# SH5_-_LOAD_MONITORING_1.net
KiCad netlist of a schematic drawn in Altium Designer
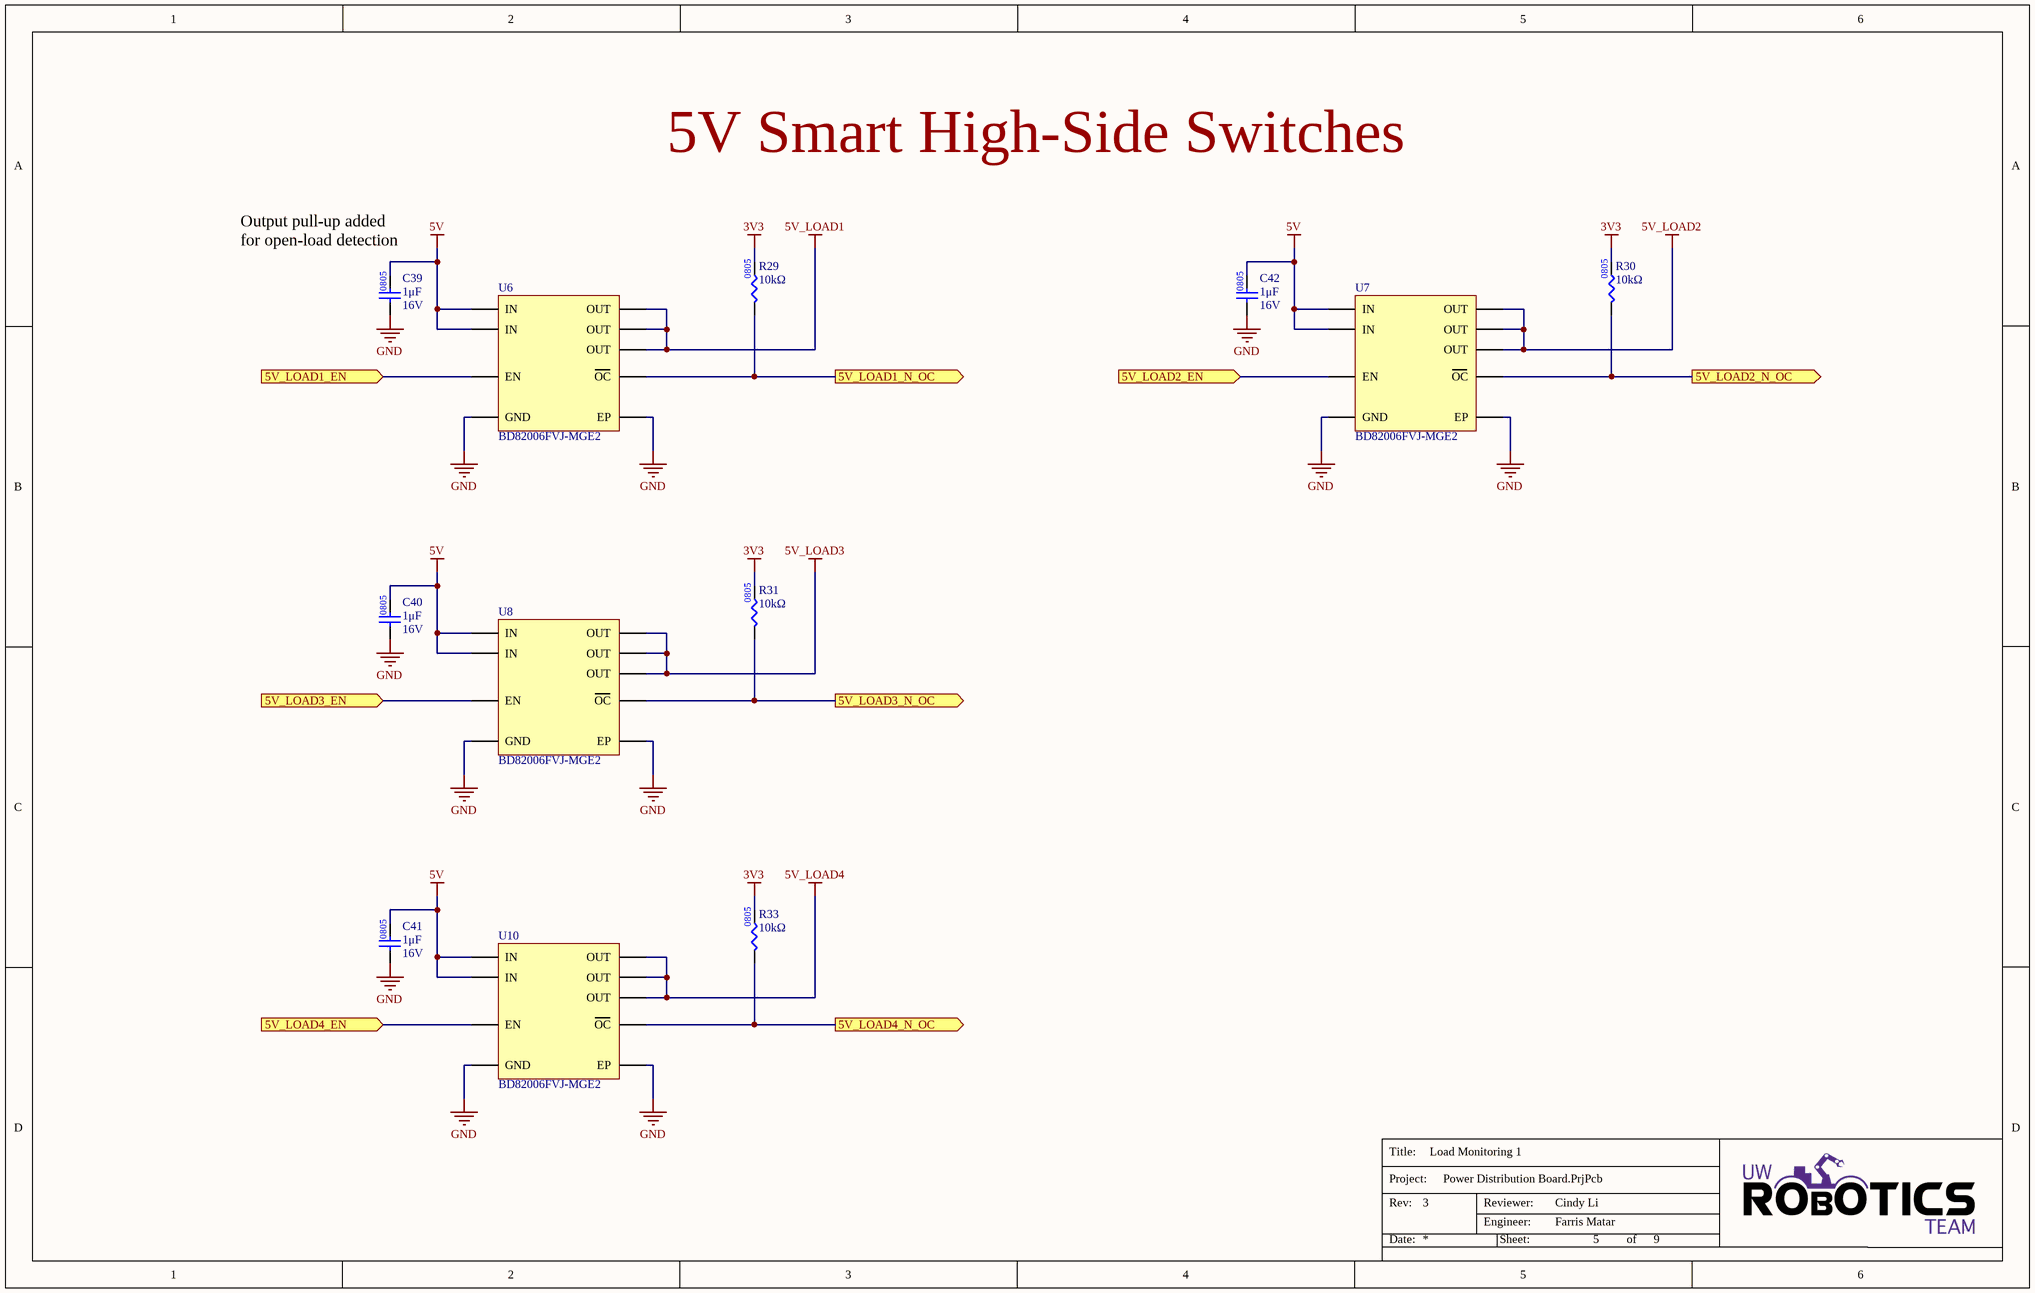
[diagram p0: SH5 - LOAD MONITORING 1.SchDoc]

(export (version "E")
  (design (tool "Eeschema 10.0.6"))
  (components
    (comp (ref "C39")
      (value "1μF")
      (footprint "CAP0805")
      (description "CAP CER 1UF 16V X7R 0805")
      (fields (field (name "VOLTAGE RATING") "16V") (field (name "Comment") "CAP_1uF_16V_0805"))
      (libsource (lib "UWRT_Schematic_Library_2020") (part "CAP_1uF_16V_0805"))
    )
    (comp (ref "C40")
      (value "1μF")
      (footprint "CAP0805")
      (description "CAP CER 1UF 16V X7R 0805")
      (fields (field (name "VOLTAGE RATING") "16V") (field (name "Comment") "CAP_1uF_16V_0805"))
      (libsource (lib "UWRT_Schematic_Library_2020") (part "CAP_1uF_16V_0805"))
    )
    (comp (ref "C41")
      (value "1μF")
      (footprint "CAP0805")
      (description "CAP CER 1UF 16V X7R 0805")
      (fields (field (name "VOLTAGE RATING") "16V") (field (name "Comment") "CAP_1uF_16V_0805"))
      (libsource (lib "UWRT_Schematic_Library_2020") (part "CAP_1uF_16V_0805"))
    )
    (comp (ref "C42")
      (value "1μF")
      (footprint "CAP0805")
      (description "CAP CER 1UF 16V X7R 0805")
      (fields (field (name "VOLTAGE RATING") "16V") (field (name "Comment") "CAP_1uF_16V_0805"))
      (libsource (lib "UWRT_Schematic_Library_2020") (part "CAP_1uF_16V_0805"))
    )
    (comp (ref "R29")
      (value "10kΩ")
      (footprint "RES0805")
      (description "RES 10K OHM 5% 1/8W 0805")
      (fields (field (name "LCSC PART #") "C17414") (field (name "Comment") "RES_10kΩ_0805_5%"))
      (libsource (lib "UWRT_Schematic_Library_2020") (part "RES_10kΩ_0805_5%"))
    )
    (comp (ref "R30")
      (value "10kΩ")
      (footprint "RES0805")
      (description "RES 10K OHM 5% 1/8W 0805")
      (fields (field (name "LCSC PART #") "C17414") (field (name "Comment") "RES_10kΩ_0805_5%"))
      (libsource (lib "UWRT_Schematic_Library_2020") (part "RES_10kΩ_0805_5%"))
    )
    (comp (ref "R31")
      (value "10kΩ")
      (footprint "RES0805")
      (description "RES 10K OHM 5% 1/8W 0805")
      (fields (field (name "LCSC PART #") "C17414") (field (name "Comment") "RES_10kΩ_0805_5%"))
      (libsource (lib "UWRT_Schematic_Library_2020") (part "RES_10kΩ_0805_5%"))
    )
    (comp (ref "R33")
      (value "10kΩ")
      (footprint "RES0805")
      (description "RES 10K OHM 5% 1/8W 0805")
      (fields (field (name "LCSC PART #") "C17414") (field (name "Comment") "RES_10kΩ_0805_5%"))
      (libsource (lib "UWRT_Schematic_Library_2020") (part "RES_10kΩ_0805_5%"))
    )
    (comp (ref "U6")
      (value "BD82006FVJ-MGE2")
      (footprint "8-TSSOP-BJ")
      (description "IC PWR SWITCH N-CHAN 1:1 8TSSOP")
      (fields (field (name "MANUFACTURER PART NUMBER 1") "BD82006FVJ-MGE2"))
      (libsource (lib "UWRT_Schematic_Library_2020") (part "BD82006FVJ-MGE2"))
    )
    (comp (ref "U7")
      (value "BD82006FVJ-MGE2")
      (footprint "8-TSSOP-BJ")
      (description "IC PWR SWITCH N-CHAN 1:1 8TSSOP")
      (fields (field (name "MANUFACTURER PART NUMBER 1") "BD82006FVJ-MGE2"))
      (libsource (lib "UWRT_Schematic_Library_2020") (part "BD82006FVJ-MGE2"))
    )
    (comp (ref "U8")
      (value "BD82006FVJ-MGE2")
      (footprint "8-TSSOP-BJ")
      (description "IC PWR SWITCH N-CHAN 1:1 8TSSOP")
      (fields (field (name "MANUFACTURER PART NUMBER 1") "BD82006FVJ-MGE2"))
      (libsource (lib "UWRT_Schematic_Library_2020") (part "BD82006FVJ-MGE2"))
    )
    (comp (ref "U10")
      (value "BD82006FVJ-MGE2")
      (footprint "8-TSSOP-BJ")
      (description "IC PWR SWITCH N-CHAN 1:1 8TSSOP")
      (fields (field (name "MANUFACTURER PART NUMBER 1") "BD82006FVJ-MGE2"))
      (libsource (lib "UWRT_Schematic_Library_2020") (part "BD82006FVJ-MGE2"))
    )
  )
  (nets
    (net (code "1") (name "/5V_LOAD1_EN") (class "Default")
      (node (ref "U6") (pin "4") (pinfunction "EN_4") (pintype "passive"))
    )
    (net (code "2") (name "/5V_LOAD1_N_OC") (class "Default")
      (node (ref "R29") (pin "1") (pinfunction "1_1") (pintype "passive"))
      (node (ref "U6") (pin "8") (pinfunction "OC_8") (pintype "passive"))
    )
    (net (code "3") (name "/5V_LOAD2_EN") (class "Default")
      (node (ref "U7") (pin "4") (pinfunction "EN_4") (pintype "passive"))
    )
    (net (code "4") (name "/5V_LOAD2_N_OC") (class "Default")
      (node (ref "R30") (pin "1") (pinfunction "1_1") (pintype "passive"))
      (node (ref "U7") (pin "8") (pinfunction "OC_8") (pintype "passive"))
    )
    (net (code "5") (name "/5V_LOAD3_EN") (class "Default")
      (node (ref "U8") (pin "4") (pinfunction "EN_4") (pintype "passive"))
    )
    (net (code "6") (name "/5V_LOAD3_N_OC") (class "Default")
      (node (ref "R31") (pin "1") (pinfunction "1_1") (pintype "passive"))
      (node (ref "U8") (pin "8") (pinfunction "OC_8") (pintype "passive"))
    )
    (net (code "7") (name "/5V_LOAD4_EN") (class "Default")
      (node (ref "U10") (pin "4") (pinfunction "EN_4") (pintype "passive"))
    )
    (net (code "8") (name "/5V_LOAD4_N_OC") (class "Default")
      (node (ref "R33") (pin "1") (pinfunction "1_1") (pintype "passive"))
      (node (ref "U10") (pin "8") (pinfunction "OC_8") (pintype "passive"))
    )
    (net (code "9") (name "3V3") (class "Default")
      (node (ref "R29") (pin "2") (pinfunction "2_2") (pintype "passive"))
      (node (ref "R30") (pin "2") (pinfunction "2_2") (pintype "passive"))
      (node (ref "R31") (pin "2") (pinfunction "2_2") (pintype "passive"))
      (node (ref "R33") (pin "2") (pinfunction "2_2") (pintype "passive"))
    )
    (net (code "10") (name "5V") (class "Default")
      (node (ref "C39") (pin "2") (pinfunction "2_2") (pintype "passive"))
      (node (ref "C40") (pin "2") (pinfunction "2_2") (pintype "passive"))
      (node (ref "C41") (pin "2") (pinfunction "2_2") (pintype "passive"))
      (node (ref "C42") (pin "2") (pinfunction "2_2") (pintype "passive"))
      (node (ref "U10") (pin "2") (pinfunction "IN_2") (pintype "passive"))
      (node (ref "U10") (pin "3") (pinfunction "IN_3") (pintype "passive"))
      (node (ref "U6") (pin "2") (pinfunction "IN_2") (pintype "passive"))
      (node (ref "U6") (pin "3") (pinfunction "IN_3") (pintype "passive"))
      (node (ref "U7") (pin "2") (pinfunction "IN_2") (pintype "passive"))
      (node (ref "U7") (pin "3") (pinfunction "IN_3") (pintype "passive"))
      (node (ref "U8") (pin "2") (pinfunction "IN_2") (pintype "passive"))
      (node (ref "U8") (pin "3") (pinfunction "IN_3") (pintype "passive"))
    )
    (net (code "11") (name "5V_LOAD1") (class "Default")
      (node (ref "U6") (pin "5") (pinfunction "OUT_5") (pintype "passive"))
      (node (ref "U6") (pin "6") (pinfunction "OUT_6") (pintype "passive"))
      (node (ref "U6") (pin "7") (pinfunction "OUT_7") (pintype "passive"))
    )
    (net (code "12") (name "5V_LOAD2") (class "Default")
      (node (ref "U7") (pin "5") (pinfunction "OUT_5") (pintype "passive"))
      (node (ref "U7") (pin "6") (pinfunction "OUT_6") (pintype "passive"))
      (node (ref "U7") (pin "7") (pinfunction "OUT_7") (pintype "passive"))
    )
    (net (code "13") (name "5V_LOAD3") (class "Default")
      (node (ref "U8") (pin "5") (pinfunction "OUT_5") (pintype "passive"))
      (node (ref "U8") (pin "6") (pinfunction "OUT_6") (pintype "passive"))
      (node (ref "U8") (pin "7") (pinfunction "OUT_7") (pintype "passive"))
    )
    (net (code "14") (name "5V_LOAD4") (class "Default")
      (node (ref "U10") (pin "5") (pinfunction "OUT_5") (pintype "passive"))
      (node (ref "U10") (pin "6") (pinfunction "OUT_6") (pintype "passive"))
      (node (ref "U10") (pin "7") (pinfunction "OUT_7") (pintype "passive"))
    )
    (net (code "15") (name "GND") (class "Default")
      (node (ref "C39") (pin "1") (pinfunction "1_1") (pintype "passive"))
      (node (ref "C40") (pin "1") (pinfunction "1_1") (pintype "passive"))
      (node (ref "C41") (pin "1") (pinfunction "1_1") (pintype "passive"))
      (node (ref "C42") (pin "1") (pinfunction "1_1") (pintype "passive"))
      (node (ref "U10") (pin "1") (pinfunction "GND_1") (pintype "passive"))
      (node (ref "U10") (pin "9") (pinfunction "EP_9") (pintype "passive"))
      (node (ref "U6") (pin "1") (pinfunction "GND_1") (pintype "passive"))
      (node (ref "U6") (pin "9") (pinfunction "EP_9") (pintype "passive"))
      (node (ref "U7") (pin "1") (pinfunction "GND_1") (pintype "passive"))
      (node (ref "U7") (pin "9") (pinfunction "EP_9") (pintype "passive"))
      (node (ref "U8") (pin "1") (pinfunction "GND_1") (pintype "passive"))
      (node (ref "U8") (pin "9") (pinfunction "EP_9") (pintype "passive"))
    )
  )
)
